# esc.net
KiCad netlist of a schematic drawn in Altium Designer
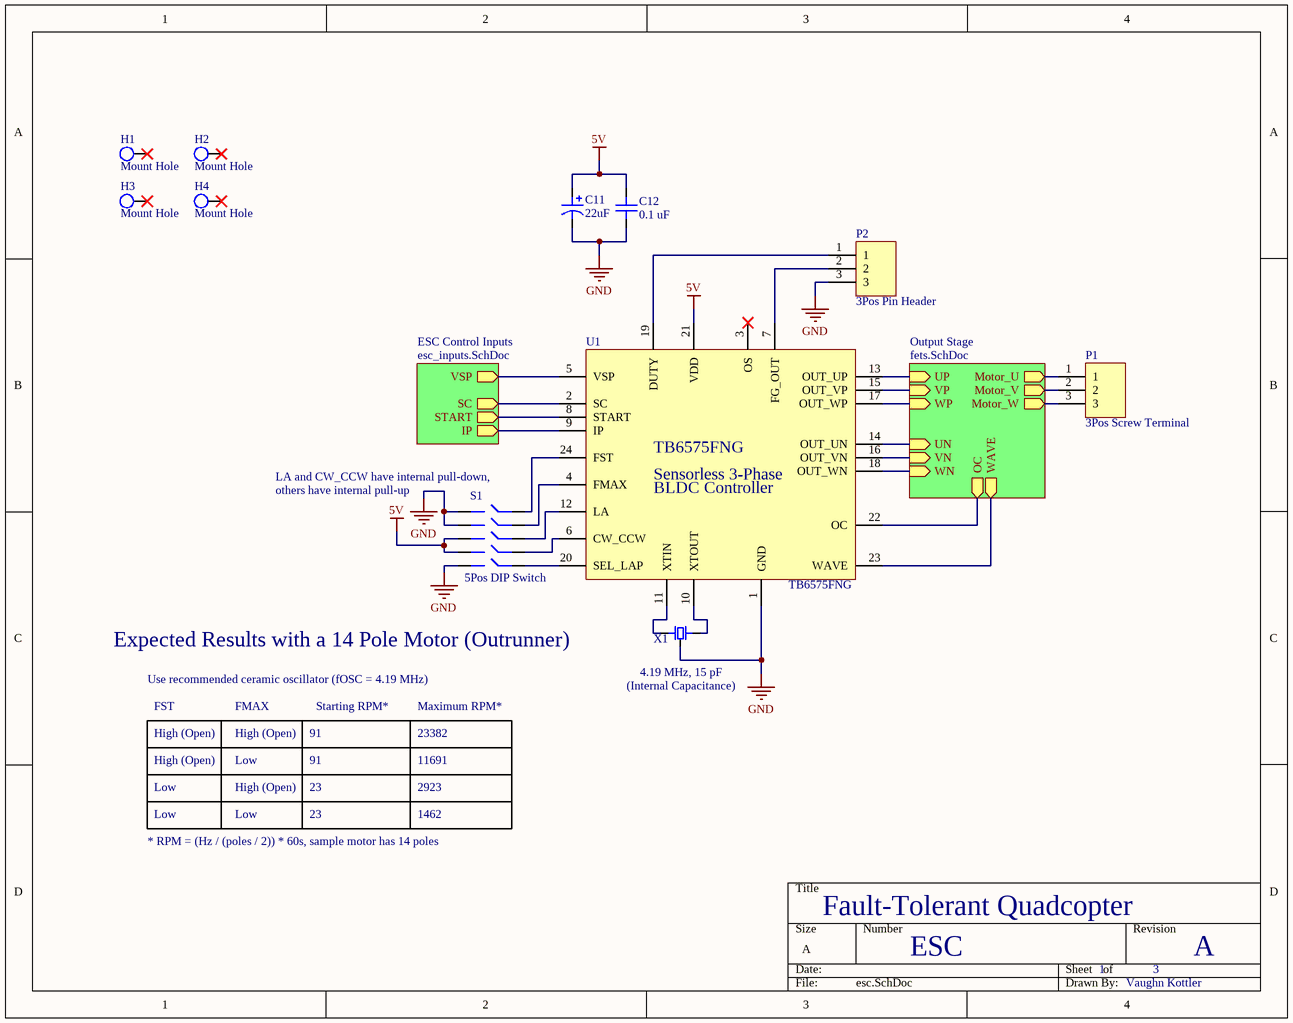
[diagram p0: esc.SchDoc]

(export (version "E")
  (design (tool "Eeschema 10.0.6"))
  (components
    (comp (ref "C11")
      (value "22uF")
      (footprint "CAP-CAN-5.3x5.3")
      (description "±20%, 5.3mm x 5.3mm")
      (libsource (lib "passive") (part "CAP-CAN-22uF-35V"))
    )
    (comp (ref "C12")
      (value "0.1 uF")
      (footprint "CAP-CER-0805-SHORT")
      (description "10%, 0805")
      (libsource (lib "passive") (part "CAP-CER-0.1uF-25V"))
    )
    (comp (ref "H1")
      (value "Mount Hole")
      (footprint "m2 Mount Hole")
      (libsource (lib "connector") (part "Mount Hole"))
    )
    (comp (ref "H2")
      (value "Mount Hole")
      (footprint "m2 Mount Hole")
      (libsource (lib "connector") (part "Mount Hole"))
    )
    (comp (ref "H3")
      (value "Mount Hole")
      (footprint "m2 Mount Hole")
      (libsource (lib "connector") (part "Mount Hole"))
    )
    (comp (ref "H4")
      (value "Mount Hole")
      (footprint "m2 Mount Hole")
      (libsource (lib "connector") (part "Mount Hole"))
    )
    (comp (ref "P1")
      (value "3Pos Screw Terminal")
      (footprint "3Pos Screw Terminal")
      (description "0.2\" Pitch 1x3")
      (libsource (lib "connector") (part "3Pos Screw Terminal"))
    )
    (comp (ref "P2")
      (value "3Pos Pin Header")
      (footprint "3Pos Pin Header F RA R")
      (description "0.1\" Pitch 1x3")
      (libsource (lib "connector") (part "3Pos Pin Header"))
    )
    (comp (ref "S1")
      (value "5Pos DIP Switch")
      (footprint "DIP-SW-5")
      (description "5 Position 0.1\" SMT Dip Switch")
      (libsource (lib "connector") (part "5Pos DIP Switch"))
    )
    (comp (ref "U1")
      (value "TB6575FNG")
      (footprint "SSOP24-0.65")
      (description "Sensorless 3-Phase BLDC Controller")
      (libsource (lib "ic") (part "TB6575FNG"))
    )
    (comp (ref "X1")
      (value "4.19 MHz, 15 pF")
      (footprint "CSTCR")
      (description "Ceramic, 3-SMD, Built-In Capacitance")
      (libsource (lib "passive") (part "XTAL-4.19MHz-15pF"))
    )
  )
  (nets
    (net (code "1") (name "/IP") (class "Default")
      (node (ref "U1") (pin "9") (pinfunction "IP_9") (pintype "passive"))
    )
    (net (code "2") (name "/Motor_U") (class "Default")
      (node (ref "P1") (pin "1") (pinfunction "1_1") (pintype "passive"))
    )
    (net (code "3") (name "/Motor_V") (class "Default")
      (node (ref "P1") (pin "2") (pinfunction "2_2") (pintype "passive"))
    )
    (net (code "4") (name "/Motor_W") (class "Default")
      (node (ref "P1") (pin "3") (pinfunction "3_3") (pintype "passive"))
    )
    (net (code "5") (name "/OC") (class "Default")
      (node (ref "U1") (pin "22") (pinfunction "OC_22") (pintype "passive"))
    )
    (net (code "6") (name "/SC") (class "Default")
      (node (ref "U1") (pin "2") (pinfunction "SC_2") (pintype "passive"))
    )
    (net (code "7") (name "/START") (class "Default")
      (node (ref "U1") (pin "8") (pinfunction "START_8") (pintype "passive"))
    )
    (net (code "8") (name "/UN") (class "Default")
      (node (ref "U1") (pin "14") (pinfunction "OUT_UN_14") (pintype "passive"))
    )
    (net (code "9") (name "/UP") (class "Default")
      (node (ref "U1") (pin "13") (pinfunction "OUT_UP_13") (pintype "passive"))
    )
    (net (code "10") (name "/VN") (class "Default")
      (node (ref "U1") (pin "16") (pinfunction "OUT_VN_16") (pintype "passive"))
    )
    (net (code "11") (name "/VP") (class "Default")
      (node (ref "U1") (pin "15") (pinfunction "OUT_VP_15") (pintype "passive"))
    )
    (net (code "12") (name "/VSP") (class "Default")
      (node (ref "U1") (pin "5") (pinfunction "VSP_5") (pintype "passive"))
    )
    (net (code "13") (name "/WAVE") (class "Default")
      (node (ref "U1") (pin "23") (pinfunction "WAVE_23") (pintype "passive"))
    )
    (net (code "14") (name "/WN") (class "Default")
      (node (ref "U1") (pin "18") (pinfunction "OUT_WN_18") (pintype "passive"))
    )
    (net (code "15") (name "/WP") (class "Default")
      (node (ref "U1") (pin "17") (pinfunction "OUT_WP_17") (pintype "passive"))
    )
    (net (code "16") (name "5V") (class "Default")
      (node (ref "C11") (pin "1") (pinfunction "1_1") (pintype "passive"))
      (node (ref "C12") (pin "2") (pinfunction "2_2") (pintype "passive"))
      (node (ref "S1") (pin "3") (pinfunction "3_3") (pintype "passive"))
      (node (ref "S1") (pin "4") (pinfunction "4_4") (pintype "passive"))
      (node (ref "U1") (pin "21") (pinfunction "VDD_21") (pintype "passive"))
    )
    (net (code "17") (name "GND") (class "Default")
      (node (ref "C11") (pin "2") (pinfunction "2_2") (pintype "passive"))
      (node (ref "C12") (pin "1") (pinfunction "1_1") (pintype "passive"))
      (node (ref "P2") (pin "3") (pinfunction "3_3") (pintype "passive"))
      (node (ref "S1") (pin "1") (pinfunction "1_1") (pintype "passive"))
      (node (ref "S1") (pin "2") (pinfunction "2_2") (pintype "passive"))
      (node (ref "S1") (pin "5") (pinfunction "5_5") (pintype "passive"))
      (node (ref "U1") (pin "1") (pinfunction "GND_1") (pintype "passive"))
      (node (ref "X1") (pin "2") (pinfunction "GND_2") (pintype "passive"))
    )
    (net (code "18") (name "Net-(U1-CW_CCW)") (class "Default")
      (node (ref "S1") (pin "7") (pinfunction "7_7") (pintype "passive"))
      (node (ref "U1") (pin "6") (pinfunction "CW_CCW_6") (pintype "passive"))
    )
    (net (code "19") (name "Net-(U1-DUTY)") (class "Default")
      (node (ref "P2") (pin "1") (pinfunction "1_1") (pintype "passive"))
      (node (ref "U1") (pin "19") (pinfunction "DUTY_19") (pintype "passive"))
    )
    (net (code "20") (name "Net-(U1-FG_OUT)") (class "Default")
      (node (ref "P2") (pin "2") (pinfunction "2_2") (pintype "passive"))
      (node (ref "U1") (pin "7") (pinfunction "FG_OUT_7") (pintype "passive"))
    )
    (net (code "21") (name "Net-(U1-FMAX)") (class "Default")
      (node (ref "S1") (pin "9") (pinfunction "9_9") (pintype "passive"))
      (node (ref "U1") (pin "4") (pinfunction "FMAX_4") (pintype "passive"))
    )
    (net (code "22") (name "Net-(U1-FST)") (class "Default")
      (node (ref "S1") (pin "10") (pinfunction "10_10") (pintype "passive"))
      (node (ref "U1") (pin "24") (pinfunction "FST_24") (pintype "passive"))
    )
    (net (code "23") (name "Net-(U1-LA)") (class "Default")
      (node (ref "S1") (pin "8") (pinfunction "8_8") (pintype "passive"))
      (node (ref "U1") (pin "12") (pinfunction "LA_12") (pintype "passive"))
    )
    (net (code "24") (name "Net-(U1-SEL_LAP)") (class "Default")
      (node (ref "S1") (pin "6") (pinfunction "6_6") (pintype "passive"))
      (node (ref "U1") (pin "20") (pinfunction "SEL_LAP_20") (pintype "passive"))
    )
    (net (code "25") (name "Net-(U1-XTIN)") (class "Default")
      (node (ref "U1") (pin "11") (pinfunction "XTIN_11") (pintype "passive"))
      (node (ref "X1") (pin "1") (pinfunction "IN_1") (pintype "passive"))
    )
    (net (code "26") (name "Net-(U1-XTOUT)") (class "Default")
      (node (ref "U1") (pin "10") (pinfunction "XTOUT_10") (pintype "passive"))
      (node (ref "X1") (pin "3") (pinfunction "OUT_3") (pintype "passive"))
    )
    (net (code "27") (name "unconnected-(H1-PadH)") (class "Default")
      (node (ref "H1") (pin "H") (pinfunction "H_H") (pintype "passive+no_connect"))
    )
    (net (code "28") (name "unconnected-(H2-PadH)") (class "Default")
      (node (ref "H2") (pin "H") (pinfunction "H_H") (pintype "passive+no_connect"))
    )
    (net (code "29") (name "unconnected-(H3-PadH)") (class "Default")
      (node (ref "H3") (pin "H") (pinfunction "H_H") (pintype "passive+no_connect"))
    )
    (net (code "30") (name "unconnected-(H4-PadH)") (class "Default")
      (node (ref "H4") (pin "H") (pinfunction "H_H") (pintype "passive+no_connect"))
    )
    (net (code "31") (name "unconnected-(U1-OS-Pad3)") (class "Default")
      (node (ref "U1") (pin "3") (pinfunction "OS_3") (pintype "passive+no_connect"))
    )
  )
)
